# 1_axis_stepper_driver_teensy_v39.net
KiCad netlist of a schematic drawn in EAGLE
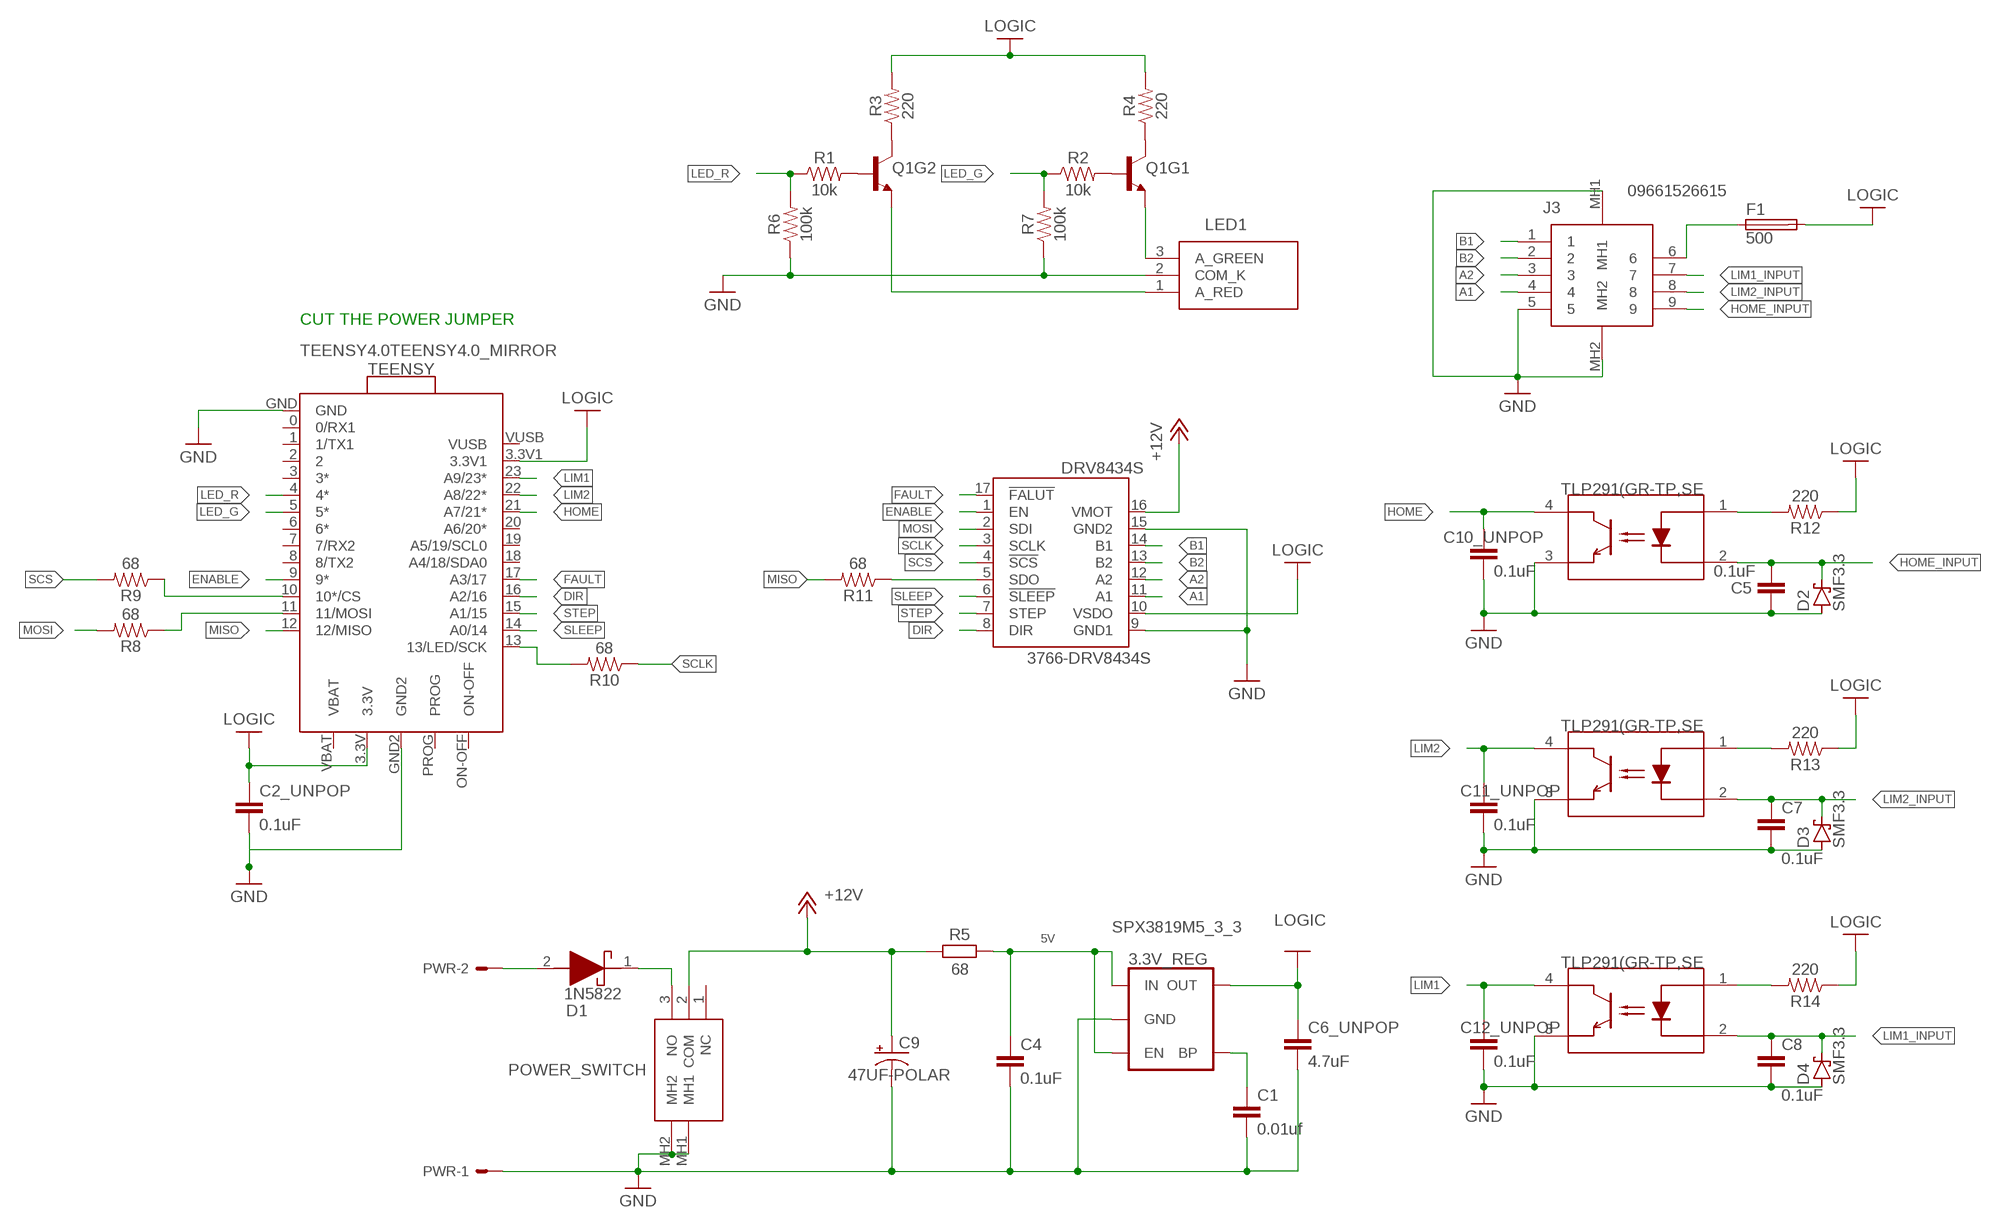
[diagram p0: schematic, sheet 1]

(export (version "E")
  (design (tool "Eeschema 10.0.6"))
  (components
    (comp (ref "3.3V_REG")
      (value "SPX3819M5_3_3")
      (footprint "eagle-import:SOT23-5")
      (libsource (lib "eagle-import") (part "V_REG_SPX3819-SOT23-5"))
    )
    (comp (ref "C1")
      (value "0.01uf")
      (footprint "eagle-import:0603")
      (libsource (lib "eagle-import") (part "0.1UF-0603-100V-10%"))
    )
    (comp (ref "C2_UNPOP")
      (value "0.1uF")
      (footprint "eagle-import:0603")
      (libsource (lib "eagle-import") (part "0.1UF-0603-100V-10%"))
    )
    (comp (ref "C4")
      (value "0.1uF")
      (footprint "eagle-import:0603")
      (libsource (lib "eagle-import") (part "0.1UF-0603-100V-10%"))
    )
    (comp (ref "C5")
      (value "0.1uF")
      (footprint "eagle-import:0603")
      (libsource (lib "eagle-import") (part "0.1UF-0603-100V-10%"))
    )
    (comp (ref "C6_UNPOP")
      (value "4.7uF")
      (footprint "eagle-import:0603")
      (libsource (lib "eagle-import") (part "4.7UF-0603-35V-(20%)"))
    )
    (comp (ref "C7")
      (value "0.1uF")
      (footprint "eagle-import:0603")
      (libsource (lib "eagle-import") (part "0.1UF-0603-100V-10%"))
    )
    (comp (ref "C8")
      (value "0.1uF")
      (footprint "eagle-import:0603")
      (libsource (lib "eagle-import") (part "0.1UF-0603-100V-10%"))
    )
    (comp (ref "C9")
      (value "47UF-POLAR")
      (footprint "eagle-import:PANASONIC_D")
      (libsource (lib "eagle-import") (part "47UF-POLAR-PANASONIC_D-50V-20%"))
    )
    (comp (ref "C10_UNPOP")
      (value "0.1uF")
      (footprint "eagle-import:0603")
      (libsource (lib "eagle-import") (part "0.1UF-0603-100V-10%"))
    )
    (comp (ref "C11_UNPOP")
      (value "0.1uF")
      (footprint "eagle-import:0603")
      (libsource (lib "eagle-import") (part "0.1UF-0603-100V-10%"))
    )
    (comp (ref "C12_UNPOP")
      (value "0.1uF")
      (footprint "eagle-import:0603")
      (libsource (lib "eagle-import") (part "0.1UF-0603-100V-10%"))
    )
    (comp (ref "D1")
      (value "1N5822")
      (footprint "eagle-import:DIOAD3070W130L950D530")
      (fields (field (name "MOUSER_PART_NUMBER") "511-1N5822"))
      (libsource (lib "eagle-import") (part "1N5822"))
    )
    (comp (ref "D2")
      (value "SMF3.3")
      (footprint "eagle-import:SOD123FL")
      (libsource (lib "eagle-import") (part "SMF5.0AT1"))
    )
    (comp (ref "D3")
      (value "SMF3.3")
      (footprint "eagle-import:SOD123FL")
      (libsource (lib "eagle-import") (part "SMF5.0AT1"))
    )
    (comp (ref "D4")
      (value "SMF3.3")
      (footprint "eagle-import:SOD123FL")
      (libsource (lib "eagle-import") (part "SMF5.0AT1"))
    )
    (comp (ref "DRV8434S")
      (value "3766-DRV8434S")
      (footprint "eagle-import:DRV8434S")
      (libsource (lib "eagle-import") (part "3766-DRV8434S"))
    )
    (comp (ref "F1")
      (value "500")
      (footprint "eagle-import:FUSC1608X60N")
      (libsource (lib "eagle-import") (part "FUSECHIP-0603(1608-METRIC)_"))
    )
    (comp (ref "J3")
      (value "09661526615")
      (footprint "eagle-import:09661526615")
      (fields (field (name "MOUSER_PART_NUMBER") "617-09661526615"))
      (libsource (lib "eagle-import") (part "09661526615"))
    )
    (comp (ref "LED1")
      (value "WP42WUM_EGW")
      (footprint "eagle-import:WP42WUMEGW")
      (fields
        (field (name "MANUFACTURER_PART_NUMBER") "WP42WUM/EGW")
        (field (name "MOUSER_PART_NUMBER") "604-WP42WUM/EGW")
      )
      (libsource (lib "eagle-import") (part "WP42WUM_EGW"))
    )
    (comp (ref "POWER_SWITCH")
      (value "200MSP1T2B2M6RE")
      (footprint "eagle-import:200MSP1T2B2M6RE")
      (fields (field (name "MOUSER_PART_NUMBER") "612-200-A2262"))
      (libsource (lib "eagle-import") (part "200MSP1T2B2M6RE"))
    )
    (comp (ref "PWR")
      (value "22-27-2021-02")
      (footprint "eagle-import:6410-02")
      (fields (field (name "MF") "MOLEX"))
      (libsource (lib "eagle-import") (part "22-?-0227-2021"))
    )
    (comp (ref "Q1")
      (value "TRANS_NPN_DUAL-MBT3904DW1T1")
      (footprint "eagle-import:SC70-6")
      (libsource (lib "eagle-import") (part "TRANS_NPN_DUAL-MBT3904DW1T1"))
    )
    (comp (ref "R1")
      (value "10k")
      (footprint "eagle-import:0603")
      (libsource (lib "eagle-import") (part "10KOHM-0603-1/10W-1%"))
    )
    (comp (ref "R2")
      (value "10k")
      (footprint "eagle-import:0603")
      (libsource (lib "eagle-import") (part "10KOHM-0603-1/10W-1%"))
    )
    (comp (ref "R3")
      (value "220")
      (footprint "eagle-import:0603")
      (libsource (lib "eagle-import") (part "220OHM-0603-1/10W-1%"))
    )
    (comp (ref "R4")
      (value "220")
      (footprint "eagle-import:0603")
      (libsource (lib "eagle-import") (part "220OHM-0603-1/10W-1%"))
    )
    (comp (ref "R5")
      (value "68")
      (footprint "eagle-import:RESC6332X71")
      (libsource (lib "eagle-import") (part "RCHIP-2512(6332-METRIC)_"))
    )
    (comp (ref "R6")
      (value "100k")
      (footprint "eagle-import:0603")
      (libsource (lib "eagle-import") (part "10KOHM-0603-1/10W-1%"))
    )
    (comp (ref "R7")
      (value "100k")
      (footprint "eagle-import:0603")
      (libsource (lib "eagle-import") (part "10KOHM-0603-1/10W-1%"))
    )
    (comp (ref "R8")
      (value "68")
      (footprint "eagle-import:0603")
      (libsource (lib "eagle-import") (part "10KOHM-0603-1/10W-1%"))
    )
    (comp (ref "R9")
      (value "68")
      (footprint "eagle-import:0603")
      (libsource (lib "eagle-import") (part "10KOHM-0603-1/10W-1%"))
    )
    (comp (ref "R10")
      (value "68")
      (footprint "eagle-import:0603")
      (libsource (lib "eagle-import") (part "10KOHM-0603-1/10W-1%"))
    )
    (comp (ref "R11")
      (value "68")
      (footprint "eagle-import:0603")
      (libsource (lib "eagle-import") (part "10KOHM-0603-1/10W-1%"))
    )
    (comp (ref "R12")
      (value "220")
      (footprint "eagle-import:0603")
      (libsource (lib "eagle-import") (part "10KOHM-0603-1/10W-1%"))
    )
    (comp (ref "R13")
      (value "220")
      (footprint "eagle-import:0603")
      (libsource (lib "eagle-import") (part "10KOHM-0603-1/10W-1%"))
    )
    (comp (ref "R14")
      (value "220")
      (footprint "eagle-import:0603")
      (libsource (lib "eagle-import") (part "10KOHM-0603-1/10W-1%"))
    )
    (comp (ref "TEENSY")
      (value "TEENSY4.0TEENSY4.0_MIRROR")
      (footprint "eagle-import:TEENSY4.0_MIRROR")
      (libsource (lib "eagle-import") (part "TEENSY4.0TEENSY4.0_MIRROR"))
    )
    (comp (ref "U1")
      (value "TLP291(GR-TP,SE")
      (footprint "eagle-import:TLP291(GR-TP,SE")
      (fields
        (field (name "DIGIKEY_PART_NUMBER") "TLP291(GR-TPSECT-ND")
        (field (name "MANUFACTURER") "Toshiba Semiconductor and Storage")
        (field (name "CREATED_BY") "PCBLayout.com")
      )
      (libsource (lib "eagle-import") (part "TLP291(GR-TP,SE"))
    )
    (comp (ref "U2")
      (value "TLP291(GR-TP,SE")
      (footprint "eagle-import:TLP291(GR-TP,SE")
      (fields
        (field (name "DIGIKEY_PART_NUMBER") "TLP291(GR-TPSECT-ND")
        (field (name "MANUFACTURER") "Toshiba Semiconductor and Storage")
        (field (name "CREATED_BY") "PCBLayout.com")
      )
      (libsource (lib "eagle-import") (part "TLP291(GR-TP,SE"))
    )
    (comp (ref "U3")
      (value "TLP291(GR-TP,SE")
      (footprint "eagle-import:TLP291(GR-TP,SE")
      (fields
        (field (name "DIGIKEY_PART_NUMBER") "TLP291(GR-TPSECT-ND")
        (field (name "MANUFACTURER") "Toshiba Semiconductor and Storage")
        (field (name "CREATED_BY") "PCBLayout.com")
      )
      (libsource (lib "eagle-import") (part "TLP291(GR-TP,SE"))
    )
  )
  (nets
    (net (code "1") (name "+12V") (class "Default")
      (node (ref "C9") (pin "+") (pinfunction "+_+") (pintype "passive"))
      (node (ref "DRV8434S") (pin "16") (pinfunction "VMOT_16") (pintype "power_in"))
      (node (ref "POWER_SWITCH") (pin "2") (pinfunction "COM_2") (pintype "bidirectional"))
      (node (ref "R5") (pin "1") (pinfunction "1_1") (pintype "passive"))
    )
    (net (code "2") (name "/5V") (class "Default")
      (node (ref "3.3V_REG") (pin "1") (pinfunction "IN_1") (pintype "input"))
      (node (ref "3.3V_REG") (pin "3") (pinfunction "EN_3") (pintype "input"))
      (node (ref "C4") (pin "1") (pinfunction "1_1") (pintype "passive"))
      (node (ref "R5") (pin "2") (pinfunction "2_2") (pintype "passive"))
    )
    (net (code "3") (name "/VBAT") (class "Default")
      (node (ref "TEENSY") (pin "VBAT") (pinfunction "VBAT_VBAT") (pintype "power_in"))
    )
    (net (code "4") (name "/VUSB") (class "Default")
      (node (ref "TEENSY") (pin "VUSB") (pinfunction "VUSB_VUSB") (pintype "power_in"))
    )
    (net (code "5") (name "A1") (class "Default")
      (node (ref "DRV8434S") (pin "11") (pinfunction "A1_11") (pintype "output"))
      (node (ref "J3") (pin "4") (pinfunction "4_4") (pintype "bidirectional"))
    )
    (net (code "6") (name "A2") (class "Default")
      (node (ref "DRV8434S") (pin "12") (pinfunction "A2_12") (pintype "output"))
      (node (ref "J3") (pin "3") (pinfunction "3_3") (pintype "bidirectional"))
    )
    (net (code "7") (name "B1") (class "Default")
      (node (ref "DRV8434S") (pin "14") (pinfunction "B1_14") (pintype "output"))
      (node (ref "J3") (pin "1") (pinfunction "1_1") (pintype "bidirectional"))
    )
    (net (code "8") (name "B2") (class "Default")
      (node (ref "DRV8434S") (pin "13") (pinfunction "B2_13") (pintype "output"))
      (node (ref "J3") (pin "2") (pinfunction "2_2") (pintype "bidirectional"))
    )
    (net (code "9") (name "DIR") (class "Default")
      (node (ref "DRV8434S") (pin "8") (pinfunction "DIR_8") (pintype "input"))
      (node (ref "TEENSY") (pin "16") (pinfunction "A2/16_16") (pintype "bidirectional"))
    )
    (net (code "10") (name "ENABLE") (class "Default")
      (node (ref "DRV8434S") (pin "1") (pinfunction "EN_1") (pintype "passive"))
      (node (ref "TEENSY") (pin "9") (pinfunction "9*_9") (pintype "bidirectional"))
    )
    (net (code "11") (name "FAULT") (class "Default")
      (node (ref "DRV8434S") (pin "17") (pinfunction "~{FALUT}_17") (pintype "passive"))
      (node (ref "TEENSY") (pin "17") (pinfunction "A3/17_17") (pintype "bidirectional"))
    )
    (net (code "12") (name "GND") (class "Default")
      (node (ref "3.3V_REG") (pin "2") (pinfunction "GND_2") (pintype "input"))
      (node (ref "C1") (pin "2") (pinfunction "2_2") (pintype "passive"))
      (node (ref "C10_UNPOP") (pin "2") (pinfunction "2_2") (pintype "passive"))
      (node (ref "C11_UNPOP") (pin "2") (pinfunction "2_2") (pintype "passive"))
      (node (ref "C12_UNPOP") (pin "2") (pinfunction "2_2") (pintype "passive"))
      (node (ref "C2_UNPOP") (pin "2") (pinfunction "2_2") (pintype "passive"))
      (node (ref "C4") (pin "2") (pinfunction "2_2") (pintype "passive"))
      (node (ref "C5") (pin "2") (pinfunction "2_2") (pintype "passive"))
      (node (ref "C6_UNPOP") (pin "2") (pinfunction "2_2") (pintype "passive"))
      (node (ref "C7") (pin "2") (pinfunction "2_2") (pintype "passive"))
      (node (ref "C8") (pin "2") (pinfunction "2_2") (pintype "passive"))
      (node (ref "C9") (pin "-") (pinfunction "-_-") (pintype "passive"))
      (node (ref "D2") (pin "A") (pinfunction "A_A") (pintype "passive"))
      (node (ref "D3") (pin "A") (pinfunction "A_A") (pintype "passive"))
      (node (ref "D4") (pin "A") (pinfunction "A_A") (pintype "passive"))
      (node (ref "DRV8434S") (pin "15") (pinfunction "GND2_15") (pintype "power_in"))
      (node (ref "DRV8434S") (pin "9") (pinfunction "GND1_9") (pintype "power_in"))
      (node (ref "J3") (pin "5") (pinfunction "5_5") (pintype "bidirectional"))
      (node (ref "J3") (pin "MH1") (pinfunction "MH1_MH1") (pintype "bidirectional"))
      (node (ref "J3") (pin "MH2") (pinfunction "MH2_MH2") (pintype "bidirectional"))
      (node (ref "LED1") (pin "2") (pinfunction "COM_K_2") (pintype "bidirectional"))
      (node (ref "POWER_SWITCH") (pin "MH1") (pinfunction "MH1_MH1") (pintype "bidirectional"))
      (node (ref "POWER_SWITCH") (pin "MH2") (pinfunction "MH2_MH2") (pintype "bidirectional"))
      (node (ref "PWR") (pin "1") (pinfunction "S_1") (pintype "passive"))
      (node (ref "R6") (pin "1") (pinfunction "1_1") (pintype "passive"))
      (node (ref "R7") (pin "1") (pinfunction "1_1") (pintype "passive"))
      (node (ref "TEENSY") (pin "GND") (pinfunction "GND_GND") (pintype "power_in"))
      (node (ref "TEENSY") (pin "GND2") (pinfunction "GND2_GND2") (pintype "power_in"))
      (node (ref "U1") (pin "3") (pinfunction "EMITTER_3") (pintype "passive"))
      (node (ref "U2") (pin "3") (pinfunction "EMITTER_3") (pintype "passive"))
      (node (ref "U3") (pin "3") (pinfunction "EMITTER_3") (pintype "passive"))
    )
    (net (code "13") (name "HOME") (class "Default")
      (node (ref "C10_UNPOP") (pin "1") (pinfunction "1_1") (pintype "passive"))
      (node (ref "TEENSY") (pin "21") (pinfunction "A7/21*_21") (pintype "bidirectional"))
      (node (ref "U1") (pin "4") (pinfunction "COLLECTOR_4") (pintype "passive"))
    )
    (net (code "14") (name "HOME_INPUT") (class "Default")
      (node (ref "C5") (pin "1") (pinfunction "1_1") (pintype "passive"))
      (node (ref "D2") (pin "C") (pinfunction "C_C") (pintype "passive"))
      (node (ref "J3") (pin "9") (pinfunction "9_9") (pintype "bidirectional"))
      (node (ref "U1") (pin "2") (pinfunction "CATHODE_2") (pintype "passive"))
    )
    (net (code "15") (name "LED_G") (class "Default")
      (node (ref "R2") (pin "1") (pinfunction "1_1") (pintype "passive"))
      (node (ref "R7") (pin "2") (pinfunction "2_2") (pintype "passive"))
      (node (ref "TEENSY") (pin "5") (pinfunction "5*_5") (pintype "bidirectional"))
    )
    (net (code "16") (name "LED_R") (class "Default")
      (node (ref "R1") (pin "1") (pinfunction "1_1") (pintype "passive"))
      (node (ref "R6") (pin "2") (pinfunction "2_2") (pintype "passive"))
      (node (ref "TEENSY") (pin "4") (pinfunction "4*_4") (pintype "bidirectional"))
    )
    (net (code "17") (name "LIM1") (class "Default")
      (node (ref "C12_UNPOP") (pin "1") (pinfunction "1_1") (pintype "passive"))
      (node (ref "TEENSY") (pin "23") (pinfunction "A9/23*_23") (pintype "bidirectional"))
      (node (ref "U3") (pin "4") (pinfunction "COLLECTOR_4") (pintype "passive"))
    )
    (net (code "18") (name "LIM1_INPUT") (class "Default")
      (node (ref "C8") (pin "1") (pinfunction "1_1") (pintype "passive"))
      (node (ref "D4") (pin "C") (pinfunction "C_C") (pintype "passive"))
      (node (ref "J3") (pin "7") (pinfunction "7_7") (pintype "bidirectional"))
      (node (ref "U3") (pin "2") (pinfunction "CATHODE_2") (pintype "passive"))
    )
    (net (code "19") (name "LIM2") (class "Default")
      (node (ref "C11_UNPOP") (pin "1") (pinfunction "1_1") (pintype "passive"))
      (node (ref "TEENSY") (pin "22") (pinfunction "A8/22*_22") (pintype "bidirectional"))
      (node (ref "U2") (pin "4") (pinfunction "COLLECTOR_4") (pintype "passive"))
    )
    (net (code "20") (name "LIM2_INPUT") (class "Default")
      (node (ref "C7") (pin "1") (pinfunction "1_1") (pintype "passive"))
      (node (ref "D3") (pin "C") (pinfunction "C_C") (pintype "passive"))
      (node (ref "J3") (pin "8") (pinfunction "8_8") (pintype "bidirectional"))
      (node (ref "U2") (pin "2") (pinfunction "CATHODE_2") (pintype "passive"))
    )
    (net (code "21") (name "LOGIC") (class "Default")
      (node (ref "3.3V_REG") (pin "5") (pinfunction "OUT_5") (pintype "passive"))
      (node (ref "C2_UNPOP") (pin "1") (pinfunction "1_1") (pintype "passive"))
      (node (ref "C6_UNPOP") (pin "1") (pinfunction "1_1") (pintype "passive"))
      (node (ref "DRV8434S") (pin "10") (pinfunction "VSDO_10") (pintype "open_collector"))
      (node (ref "F1") (pin "2") (pinfunction "2_2") (pintype "passive"))
      (node (ref "R12") (pin "1") (pinfunction "1_1") (pintype "passive"))
      (node (ref "R13") (pin "1") (pinfunction "1_1") (pintype "passive"))
      (node (ref "R14") (pin "1") (pinfunction "1_1") (pintype "passive"))
      (node (ref "R3") (pin "2") (pinfunction "2_2") (pintype "passive"))
      (node (ref "R4") (pin "2") (pinfunction "2_2") (pintype "passive"))
      (node (ref "TEENSY") (pin "3.3V") (pinfunction "3.3V_3.3V") (pintype "power_in"))
      (node (ref "TEENSY") (pin "3.3V1") (pinfunction "3.3V1_3.3V1") (pintype "power_in"))
    )
    (net (code "22") (name "MISO") (class "Default")
      (node (ref "R11") (pin "2") (pinfunction "2_2") (pintype "passive"))
      (node (ref "TEENSY") (pin "12") (pinfunction "12/MISO_12") (pintype "bidirectional"))
    )
    (net (code "23") (name "MOSI") (class "Default")
      (node (ref "DRV8434S") (pin "2") (pinfunction "SDI_2") (pintype "passive"))
      (node (ref "R8") (pin "2") (pinfunction "2_2") (pintype "passive"))
    )
    (net (code "24") (name "Net-(3.3V_REG-BP)") (class "Default")
      (node (ref "3.3V_REG") (pin "4") (pinfunction "BP_4") (pintype "input"))
      (node (ref "C1") (pin "1") (pinfunction "1_1") (pintype "passive"))
    )
    (net (code "25") (name "Net-(D1-A)") (class "Default")
      (node (ref "D1") (pin "2") (pinfunction "A_2") (pintype "bidirectional"))
      (node (ref "PWR") (pin "2") (pinfunction "S_2") (pintype "passive"))
    )
    (net (code "26") (name "Net-(D1-K)") (class "Default")
      (node (ref "D1") (pin "1") (pinfunction "K_1") (pintype "bidirectional"))
      (node (ref "POWER_SWITCH") (pin "3") (pinfunction "NO_3") (pintype "bidirectional"))
    )
    (net (code "27") (name "Net-(DRV8434S-SDO)") (class "Default")
      (node (ref "DRV8434S") (pin "5") (pinfunction "SDO_5") (pintype "input"))
      (node (ref "R11") (pin "1") (pinfunction "1_1") (pintype "passive"))
    )
    (net (code "28") (name "Net-(F1-Pad1)") (class "Default")
      (node (ref "F1") (pin "1") (pinfunction "1_1") (pintype "passive"))
      (node (ref "J3") (pin "6") (pinfunction "6_6") (pintype "bidirectional"))
    )
    (net (code "29") (name "Net-(LED1-A_GREEN)") (class "Default")
      (node (ref "LED1") (pin "3") (pinfunction "A_GREEN_3") (pintype "bidirectional"))
      (node (ref "Q1") (pin "4") (pinfunction "E_4") (pintype "passive"))
    )
    (net (code "30") (name "Net-(LED1-A_RED)") (class "Default")
      (node (ref "LED1") (pin "1") (pinfunction "A_RED_1") (pintype "bidirectional"))
      (node (ref "Q1") (pin "1") (pinfunction "E_1") (pintype "passive"))
    )
    (net (code "31") (name "Net-(Q1A-B)") (class "Default")
      (node (ref "Q1") (pin "5") (pinfunction "B_5") (pintype "passive"))
      (node (ref "R2") (pin "2") (pinfunction "2_2") (pintype "passive"))
    )
    (net (code "32") (name "Net-(Q1A-C)") (class "Default")
      (node (ref "Q1") (pin "3") (pinfunction "C_3") (pintype "passive"))
      (node (ref "R4") (pin "1") (pinfunction "1_1") (pintype "passive"))
    )
    (net (code "33") (name "Net-(Q1B-B)") (class "Default")
      (node (ref "Q1") (pin "2") (pinfunction "B_2") (pintype "passive"))
      (node (ref "R1") (pin "2") (pinfunction "2_2") (pintype "passive"))
    )
    (net (code "34") (name "Net-(Q1B-C)") (class "Default")
      (node (ref "Q1") (pin "6") (pinfunction "C_6") (pintype "passive"))
      (node (ref "R3") (pin "1") (pinfunction "1_1") (pintype "passive"))
    )
    (net (code "35") (name "Net-(TEENSY-10*{slash}CS)") (class "Default")
      (node (ref "R9") (pin "1") (pinfunction "1_1") (pintype "passive"))
      (node (ref "TEENSY") (pin "10") (pinfunction "10*/CS_10") (pintype "bidirectional"))
    )
    (net (code "36") (name "Net-(TEENSY-11{slash}MOSI)") (class "Default")
      (node (ref "R8") (pin "1") (pinfunction "1_1") (pintype "passive"))
      (node (ref "TEENSY") (pin "11") (pinfunction "11/MOSI_11") (pintype "bidirectional"))
    )
    (net (code "37") (name "Net-(TEENSY-13{slash}LED{slash}SCK)") (class "Default")
      (node (ref "R10") (pin "2") (pinfunction "2_2") (pintype "passive"))
      (node (ref "TEENSY") (pin "13") (pinfunction "13/LED/SCK_13") (pintype "bidirectional"))
    )
    (net (code "38") (name "Net-(U1-ANODE)") (class "Default")
      (node (ref "R12") (pin "2") (pinfunction "2_2") (pintype "passive"))
      (node (ref "U1") (pin "1") (pinfunction "ANODE_1") (pintype "passive"))
    )
    (net (code "39") (name "Net-(U2-ANODE)") (class "Default")
      (node (ref "R13") (pin "2") (pinfunction "2_2") (pintype "passive"))
      (node (ref "U2") (pin "1") (pinfunction "ANODE_1") (pintype "passive"))
    )
    (net (code "40") (name "Net-(U3-ANODE)") (class "Default")
      (node (ref "R14") (pin "2") (pinfunction "2_2") (pintype "passive"))
      (node (ref "U3") (pin "1") (pinfunction "ANODE_1") (pintype "passive"))
    )
    (net (code "41") (name "SCLK") (class "Default")
      (node (ref "DRV8434S") (pin "3") (pinfunction "SCLK_3") (pintype "passive"))
      (node (ref "R10") (pin "1") (pinfunction "1_1") (pintype "passive"))
    )
    (net (code "42") (name "SCS") (class "Default")
      (node (ref "DRV8434S") (pin "4") (pinfunction "~{SCS}_4") (pintype "passive"))
      (node (ref "R9") (pin "2") (pinfunction "2_2") (pintype "passive"))
    )
    (net (code "43") (name "SLEEP") (class "Default")
      (node (ref "DRV8434S") (pin "6") (pinfunction "~{SLEEP}_6") (pintype "input"))
      (node (ref "TEENSY") (pin "14") (pinfunction "A0/14_14") (pintype "bidirectional"))
    )
    (net (code "44") (name "STEP") (class "Default")
      (node (ref "DRV8434S") (pin "7") (pinfunction "STEP_7") (pintype "input"))
      (node (ref "TEENSY") (pin "15") (pinfunction "A1/15_15") (pintype "bidirectional"))
    )
    (net (code "45") (name "unconnected-(POWER_SWITCH-NC-Pad1)") (class "Default")
      (node (ref "POWER_SWITCH") (pin "1") (pinfunction "NC_1") (pintype "no_connect"))
    )
    (net (code "46") (name "unconnected-(TEENSY-0{slash}RX1-Pad0)") (class "Default")
      (node (ref "TEENSY") (pin "0") (pinfunction "0/RX1_0") (pintype "bidirectional"))
    )
    (net (code "47") (name "unconnected-(TEENSY-1{slash}TX1-Pad1)") (class "Default")
      (node (ref "TEENSY") (pin "1") (pinfunction "1/TX1_1") (pintype "bidirectional"))
    )
    (net (code "48") (name "unconnected-(TEENSY-3*-Pad3)") (class "Default")
      (node (ref "TEENSY") (pin "3") (pinfunction "3*_3") (pintype "bidirectional"))
    )
    (net (code "49") (name "unconnected-(TEENSY-6*-Pad6)") (class "Default")
      (node (ref "TEENSY") (pin "6") (pinfunction "6*_6") (pintype "bidirectional"))
    )
    (net (code "50") (name "unconnected-(TEENSY-7{slash}RX2-Pad7)") (class "Default")
      (node (ref "TEENSY") (pin "7") (pinfunction "7/RX2_7") (pintype "bidirectional"))
    )
    (net (code "51") (name "unconnected-(TEENSY-8{slash}TX2-Pad8)") (class "Default")
      (node (ref "TEENSY") (pin "8") (pinfunction "8/TX2_8") (pintype "bidirectional"))
    )
    (net (code "52") (name "unconnected-(TEENSY-A4{slash}18{slash}SDA0-Pad18)") (class "Default")
      (node (ref "TEENSY") (pin "18") (pinfunction "A4/18/SDA0_18") (pintype "bidirectional"))
    )
    (net (code "53") (name "unconnected-(TEENSY-A5{slash}19{slash}SCL0-Pad19)") (class "Default")
      (node (ref "TEENSY") (pin "19") (pinfunction "A5/19/SCL0_19") (pintype "bidirectional"))
    )
    (net (code "54") (name "unconnected-(TEENSY-A6{slash}20*-Pad20)") (class "Default")
      (node (ref "TEENSY") (pin "20") (pinfunction "A6/20*_20") (pintype "bidirectional"))
    )
    (net (code "55") (name "unconnected-(TEENSY-Pad2)") (class "Default")
      (node (ref "TEENSY") (pin "2") (pinfunction "2_2") (pintype "bidirectional"))
    )
    (net (code "56") (name "unconnected-(TEENSY-PadON-OFF)") (class "Default")
      (node (ref "TEENSY") (pin "ON-OFF") (pinfunction "ON-OFF_ON-OFF") (pintype "bidirectional"))
    )
    (net (code "57") (name "unconnected-(TEENSY-PadPROG)") (class "Default")
      (node (ref "TEENSY") (pin "PROG") (pinfunction "PROG_PROG") (pintype "bidirectional"))
    )
  )
)
